# WizPoE-IO-V001.net
KiCad netlist of a schematic drawn in Altium Designer
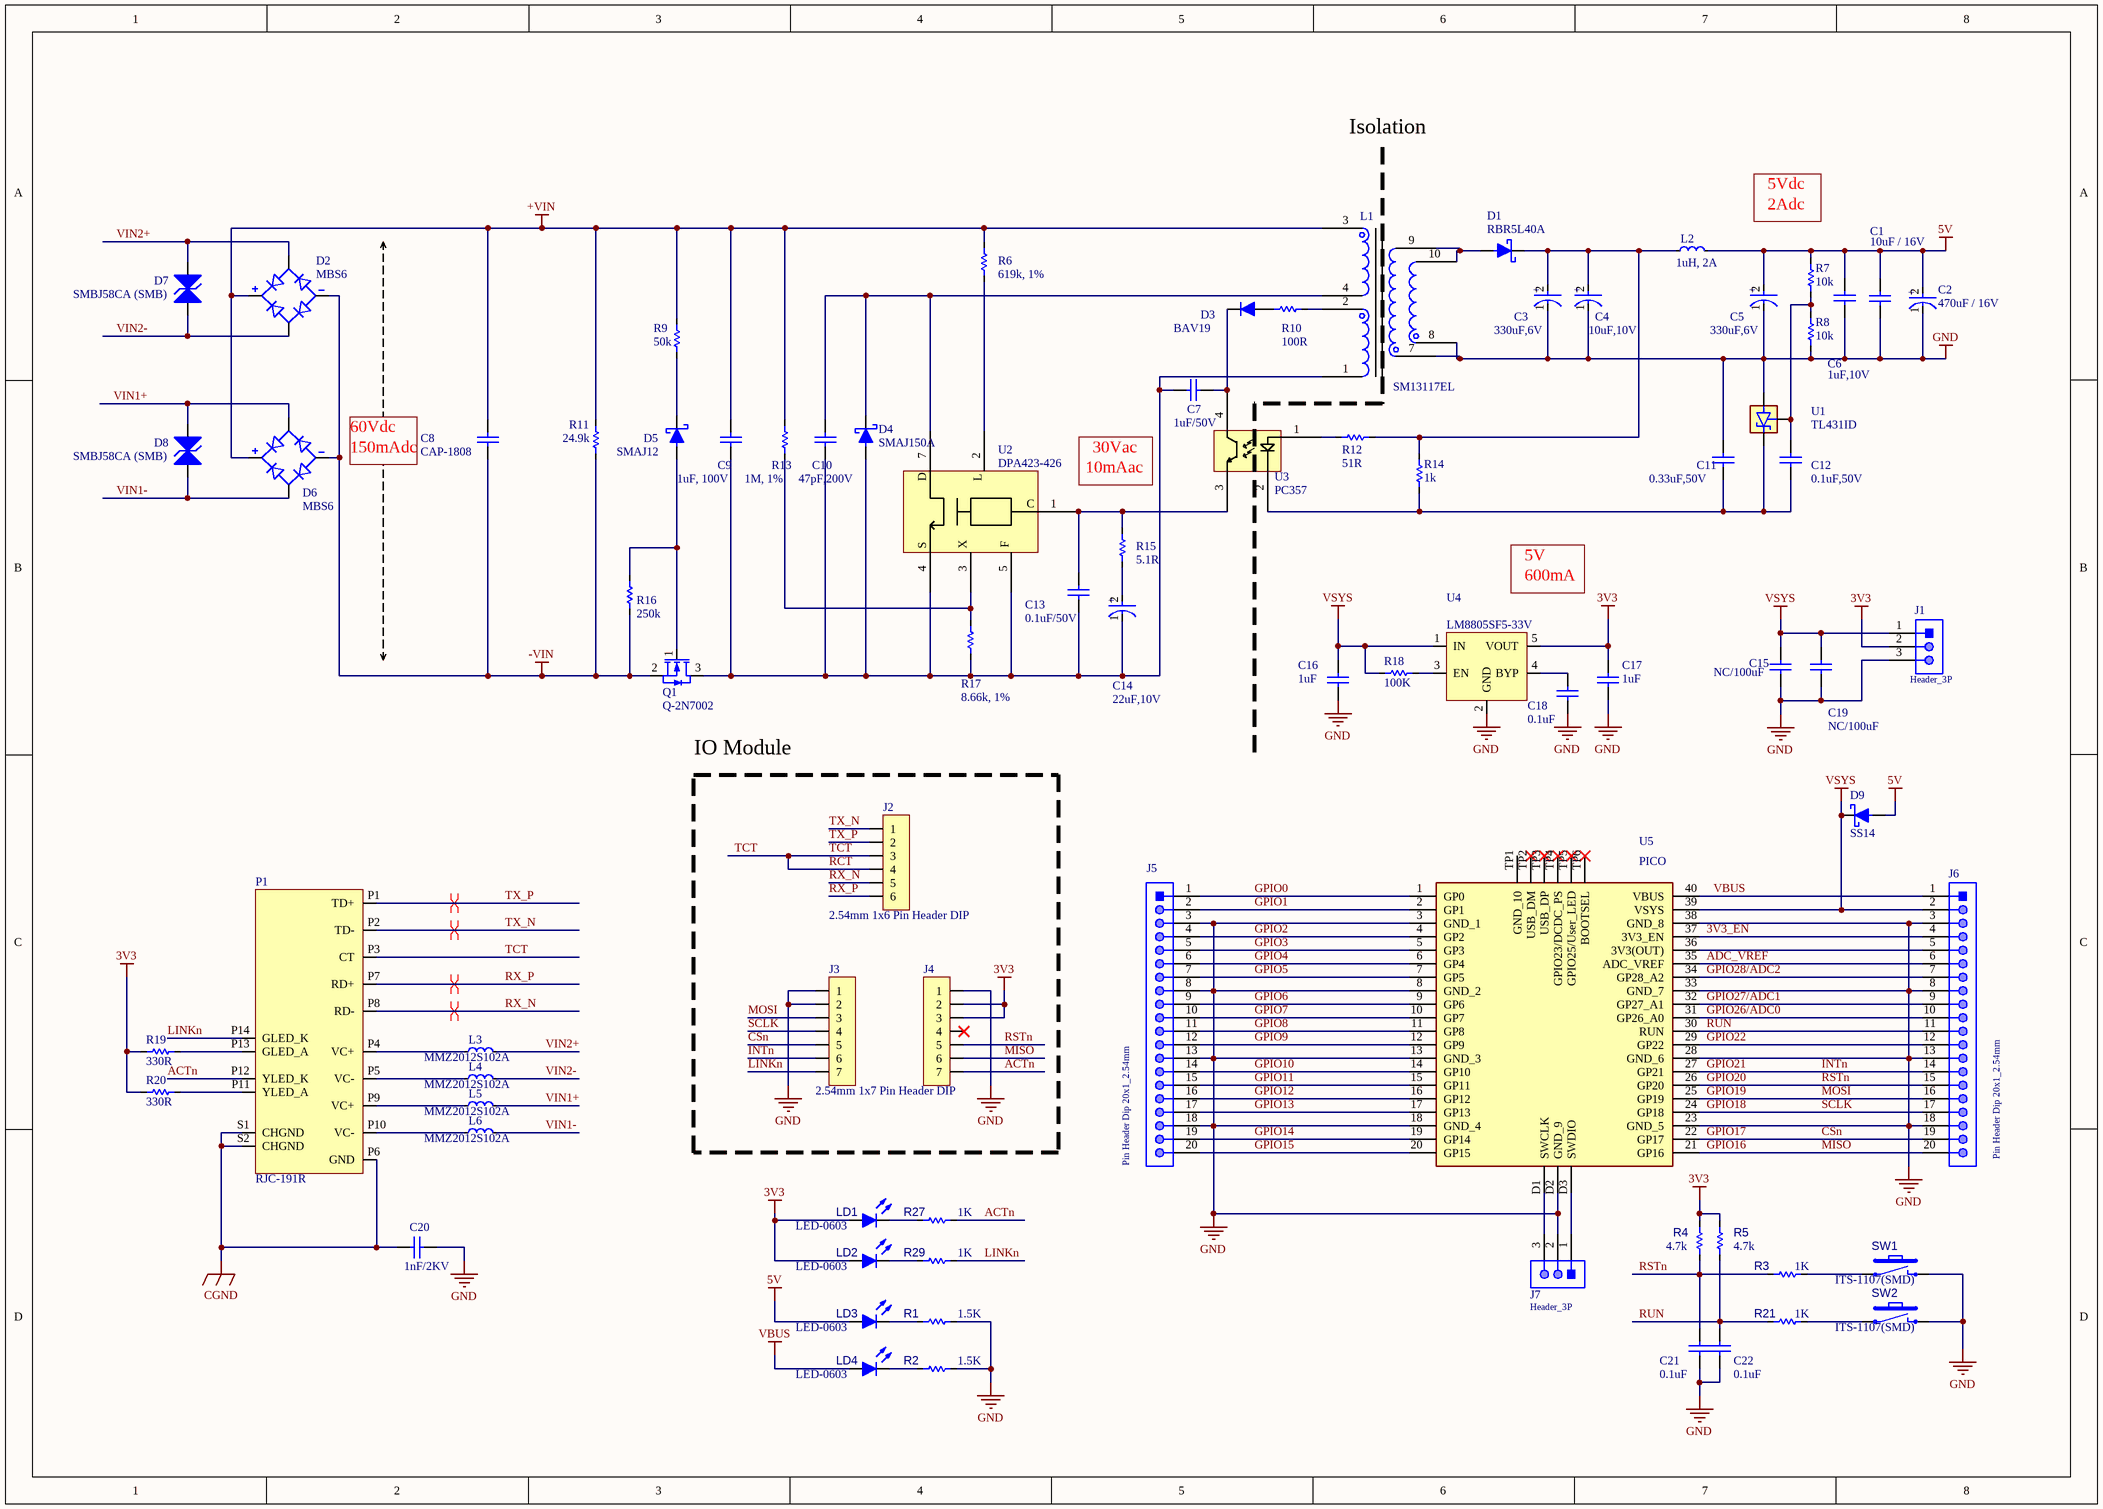
[diagram p0: WizPoE-IO-V001.SchDoc]

(export (version "E")
  (design (tool "Eeschema 10.0.6"))
  (components
    (comp (ref "C1")
      (value "10uF / 16V")
      (footprint "CAP-1808")
      (description "MLCC-1808(4520)")
      (libsource (lib "Alan_Lib") (part "CAP-1808"))
    )
    (comp (ref "C2")
      (value "470uF / 16V")
      (footprint "CAP-8.3EC")
      (description "AL-CAP D: 8.0mm SMD")
      (fields (field (name "VOLTAGE") "10V") (field (name "TOLERANCE") "20%"))
      (libsource (lib "Alan_Lib") (part "AL-CAP-D 8.0mm_SMD"))
    )
    (comp (ref "C3")
      (value "330uF,6V")
      (footprint "C6032TT(C)")
      (description "TANTAL_CASE A(3216)")
      (fields (field (name "VOLTAGE") "10V") (field (name "TOLERANCE") "20%"))
      (libsource (lib "Alan_Lib") (part "TANTAL_CASE A(3216)"))
    )
    (comp (ref "C4")
      (value "10uF,10V")
      (footprint "C3216TT(A)")
      (description "TANTAL_CASE A(3216)")
      (fields (field (name "VOLTAGE") "10V") (field (name "TOLERANCE") "20%"))
      (libsource (lib "Alan_Lib") (part "TANTAL_CASE A(3216)"))
    )
    (comp (ref "C5")
      (value "330uF,6V")
      (footprint "C3216TT(A)")
      (description "TANTAL_CASE A(3216)")
      (fields (field (name "VOLTAGE") "10V") (field (name "TOLERANCE") "20%"))
      (libsource (lib "Alan_Lib") (part "TANTAL_CASE A(3216)"))
    )
    (comp (ref "C6")
      (value "1uF,10V")
      (footprint "CAP-0603")
      (description "MLCC-0603(1608)")
      (libsource (lib "Alan_Lib") (part "CAP-0603"))
    )
    (comp (ref "C7")
      (value "1uF/50V")
      (footprint "CAP-0805")
      (description "MLCC-0805(2012)")
      (libsource (lib "Alan_Lib") (part "CAP-0805"))
    )
    (comp (ref "C8")
      (value "CAP-1808")
      (footprint "CAP-1808")
      (description "MLCC-1808(4520)")
      (libsource (lib "Alan_Lib") (part "CAP-1808"))
    )
    (comp (ref "C9")
      (value "1uF, 100V")
      (footprint "CAP-0805")
      (description "MLCC-0805(2012)")
      (libsource (lib "Alan_Lib") (part "CAP-0805"))
    )
    (comp (ref "C10")
      (value "47pF,200V")
      (footprint "CAP-0805")
      (description "MLCC-0805(2012)")
      (libsource (lib "Alan_Lib") (part "CAP-0805"))
    )
    (comp (ref "C11")
      (value "0.33uF,50V")
      (footprint "CAP-0603")
      (description "MLCC-0603(1608)")
      (libsource (lib "Alan_Lib") (part "CAP-0603"))
    )
    (comp (ref "C12")
      (value "0.1uF,50V")
      (footprint "CAP-0603")
      (description "MLCC-0603(1608)")
      (libsource (lib "Alan_Lib") (part "CAP-0603"))
    )
    (comp (ref "C13")
      (value "0.1uF/50V")
      (footprint "CAP-0805")
      (description "MLCC-0805(2012)")
      (libsource (lib "Alan_Lib") (part "CAP-0805"))
    )
    (comp (ref "C14")
      (value "22uF,10V")
      (footprint "C3216TT(A)")
      (description "TANTAL_CASE A(3216)")
      (fields (field (name "VOLTAGE") "10V") (field (name "TOLERANCE") "20%"))
      (libsource (lib "Alan_Lib") (part "TANTAL_CASE A(3216)"))
    )
    (comp (ref "C15")
      (value "NC/100uF")
      (footprint "CAP-1808")
      (description "MLCC-1808(4520)")
      (libsource (lib "Alan_Lib") (part "CAP-1808"))
    )
    (comp (ref "C16")
      (value "1uF")
      (footprint "CAP-0603")
      (description "MLCC-0603(1608)")
      (libsource (lib "Jaden_Lib") (part "CAP-0603"))
    )
    (comp (ref "C17")
      (value "1uF")
      (footprint "CAP-0603")
      (description "MLCC-0603(1608)")
      (libsource (lib "Jaden_Lib") (part "CAP-0603"))
    )
    (comp (ref "C18")
      (value "0.1uF")
      (footprint "CAP-0603")
      (description "MLCC-0603(1608)")
      (libsource (lib "Jaden_Lib") (part "CAP-0603"))
    )
    (comp (ref "C19")
      (value "NC/100uF")
      (footprint "CAP-1808")
      (description "MLCC-1808(4520)")
      (libsource (lib "Alan_Lib") (part "CAP-1808"))
    )
    (comp (ref "C20")
      (value "1nF/2KV")
      (footprint "CAP-1808")
      (description "MLCC-1808(4520)")
      (libsource (lib "Jaden_Lib") (part "CAP-1808"))
    )
    (comp (ref "C21")
      (value "0.1uF")
      (footprint "CAP-0603")
      (description "MLCC-0603(1608)")
      (libsource (lib "Jaden_Lib") (part "CAP-0603"))
    )
    (comp (ref "C22")
      (value "0.1uF")
      (footprint "CAP-0603")
      (description "MLCC-0603(1608)")
      (libsource (lib "Jaden_Lib") (part "CAP-0603"))
    )
    (comp (ref "D1")
      (value "RBR5L40A")
      (footprint "DO-214AB/SMC")
      (description "Silicon Schottky Diode")
      (libsource (lib "Alan_Lib") (part "DIODE-Shottky (SOD-323)"))
    )
    (comp (ref "D2") (value "MBS6") (footprint "TO-269AA(MBS)") (libsource (lib "Alan_Lib") (part "MBS6")))
    (comp (ref "D3")
      (value "BAV19")
      (footprint "SOD-123(1-C,2-A)")
      (description "Silicon Schottky Diode")
      (libsource (lib "Scott_lib") (part "DIODE-BAT60A"))
    )
    (comp (ref "D4")
      (value "SMAJ150A")
      (footprint "DO-214AC/SMA")
      (description "Silicon Schottky Diode")
      (libsource (lib "Alan_Lib") (part "DIODE-Shottky (SOD-323)"))
    )
    (comp (ref "D5")
      (value "SMAJ12")
      (footprint "DO-214AC/SMA")
      (description "Silicon Schottky Diode")
      (libsource (lib "Alan_Lib") (part "DIODE-Shottky (SOD-323)"))
    )
    (comp (ref "D6") (value "MBS6") (footprint "TO-269AA(MBS)") (libsource (lib "Alan_Lib") (part "MBS6")))
    (comp (ref "D7")
      (value "SMBJ58CA (SMB)")
      (footprint "DO-214AA/SMB(TVS)")
      (fields
        (field (name "PARTNUMBER") "SMAJ58CA-E3/61")
        (field (name "MANUFACTURER") "Vishay Semiconductor")
        (field (name "MANUFACTURER_1") "Vishay Semiconductors")
      )
      (libsource (lib "Jaden_Lib") (part "DIODE-TVS (SMB)"))
    )
    (comp (ref "D8")
      (value "SMBJ58CA (SMB)")
      (footprint "DO-214AA/SMB(TVS)")
      (fields
        (field (name "PARTNUMBER") "SMAJ58CA-E3/61")
        (field (name "MANUFACTURER") "Vishay Semiconductor")
        (field (name "MANUFACTURER_1") "Vishay Semiconductors")
      )
      (libsource (lib "Jaden_Lib") (part "DIODE-TVS (SMB)"))
    )
    (comp (ref "D9")
      (value "SS14")
      (footprint "DO-214AC/SMA")
      (description "DIODE SCHOTTKY 40V 1A SMA")
      (fields
        (field (name "MANUFACTURER") "ON Semiconductor")
        (field (name "OCTOPART") "https://octopart.com/ss14-on+semiconductor-29205033")
      )
      (libsource (lib "Jaden_Lib") (part "DIODE-Shottky SMA(DO-214AC)"))
    )
    (comp (ref "J1")
      (value "Header_3P")
      (footprint "IDC-1X3")
      (description "THT Vertical Pin Header WR-PHD, Pitch 2.54 mm, Single Row, 3 pins")
      (fields
        (field (name "PART NUMBER") "61300311121")
        (field (name "MANUFACTURER") "Wurth Elektronik")
        (field (name "PUBLISHER") "WurthElektronik")
      )
      (libsource (lib "Alan_Lib") (part "Pin Header 3x1_2.54mm"))
    )
    (comp (ref "J2")
      (value "2.54mm 1x6 Pin Header DIP")
      (footprint "IDC-1X6")
      (libsource (lib "Scott_lib") (part "2.54mm 1x6 Pin Header DIP"))
    )
    (comp (ref "J3")
      (value "2.54mm 1x7 Pin Header DIP")
      (footprint "IDC-1X7")
      (libsource (lib "") (part "2.54mm 1x7 Pin Header DIP_1"))
    )
    (comp (ref "J4")
      (value "2.54mm 1x7 Pin Header DIP")
      (footprint "IDC-1X7-1")
      (libsource (lib "Scott_lib") (part "2.54mm 1x7 Pin Header DIP"))
    )
    (comp (ref "J5")
      (value "Pin Header Dip 20x1_2.54mm")
      (footprint "IDC-1X20")
      (description "THT Vertical Pin Header WR-PHD, Pitch 2.54 mm, Single Row, 20 pins")
      (fields
        (field (name "MANUFACTURER") "Wurth Elektronik")
        (field (name "PART NUMBER") "61302011121")
        (field (name "PUBLISHER") "WurthElektronik")
      )
      (libsource (lib "Jaden_Lib") (part "Pin Header 20x1_2.54mm"))
    )
    (comp (ref "J6")
      (value "Pin Header Dip 20x1_2.54mm")
      (footprint "IDC-1X20")
      (description "THT Vertical Pin Header WR-PHD, Pitch 2.54 mm, Single Row, 20 pins")
      (fields
        (field (name "MANUFACTURER") "Wurth Elektronik")
        (field (name "PART NUMBER") "61302011121")
        (field (name "PUBLISHER") "WurthElektronik")
      )
      (libsource (lib "Jaden_Lib") (part "Pin Header 20x1_2.54mm"))
    )
    (comp (ref "J7")
      (value "Header_3P")
      (footprint "IDC-1X3")
      (description "THT Vertical Pin Header WR-PHD, Pitch 2.54 mm, Single Row, 3 pins")
      (fields
        (field (name "PART NUMBER") "61300311121")
        (field (name "MANUFACTURER") "Wurth Elektronik")
        (field (name "PUBLISHER") "WurthElektronik")
      )
      (libsource (lib "") (part "Pin Header 3x1_2.54mm_1"))
    )
    (comp (ref "L1")
      (value "SM13117EL")
      (footprint "SM13117EL")
      (libsource (lib "Alan_Lib") (part "SM13117EL"))
    )
    (comp (ref "L2")
      (value "1uH, 2A")
      (footprint "IND-0805")
      (description "Inductor 0805(2012)")
      (libsource (lib "Alan_Lib") (part "IND-0805"))
    )
    (comp (ref "L3")
      (value "MMZ2012S102A")
      (footprint "IND-0805")
      (description "Inductor 0603(1608)")
      (libsource (lib "Jaden_Lib") (part "IND-0603"))
    )
    (comp (ref "L4")
      (value "MMZ2012S102A")
      (footprint "IND-0805")
      (description "Inductor 0603(1608)")
      (libsource (lib "Jaden_Lib") (part "IND-0603"))
    )
    (comp (ref "L5")
      (value "MMZ2012S102A")
      (footprint "IND-0805")
      (description "Inductor 0603(1608)")
      (libsource (lib "Jaden_Lib") (part "IND-0603"))
    )
    (comp (ref "L6")
      (value "MMZ2012S102A")
      (footprint "IND-0805")
      (description "Inductor 0603(1608)")
      (libsource (lib "Jaden_Lib") (part "IND-0603"))
    )
    (comp (ref "LD1")
      (value "LED-0603")
      (footprint "LED-0603-RED")
      (libsource (lib "Scott_lib") (part "LED-0603"))
    )
    (comp (ref "LD2")
      (value "LED-0603")
      (footprint "LED-0603-RED")
      (libsource (lib "Scott_lib") (part "LED-0603"))
    )
    (comp (ref "LD3")
      (value "LED-0603")
      (footprint "LED-0603-RED")
      (libsource (lib "Scott_lib") (part "LED-0603"))
    )
    (comp (ref "LD4")
      (value "LED-0603")
      (footprint "LED-0603-RED")
      (libsource (lib "Scott_lib") (part "LED-0603"))
    )
    (comp (ref "P1")
      (value "RJC-191R")
      (footprint "RJC-191R")
      (description "PoE RJ45")
      (libsource (lib "Jaden_Lib") (part "RJC-191R"))
    )
    (comp (ref "Q1")
      (value "Q-2N7002")
      (footprint "SOT23-3L")
      (description "N-Channel 60-V (D-S) MOSFET")
      (libsource (lib "Alan_Lib") (part "Q-2N7002"))
    )
    (comp (ref "R1")
      (value "1.5K")
      (footprint "RES-0603")
      (description "RES0603")
      (libsource (lib "Scott_lib") (part "RES-0603"))
    )
    (comp (ref "R2")
      (value "1.5K")
      (footprint "RES-0603")
      (description "RES0603")
      (libsource (lib "Scott_lib") (part "RES-0603"))
    )
    (comp (ref "R3")
      (value "1K")
      (footprint "RES-0603")
      (description "RES0603")
      (libsource (lib "Alan_Lib") (part "RES-0603"))
    )
    (comp (ref "R4")
      (value "4.7k")
      (footprint "RES-0603")
      (description "RES0603")
      (libsource (lib "Alan_Lib") (part "RES-0603"))
    )
    (comp (ref "R5")
      (value "4.7k")
      (footprint "RES-0603")
      (description "RES0603")
      (libsource (lib "Alan_Lib") (part "RES-0603"))
    )
    (comp (ref "R6")
      (value "619k, 1%")
      (footprint "RES-0603")
      (description "Chip Resistor 0603(1608)")
      (fields (field (name "TOLERANCE") "1%") (field (name "MANUFACTURER") "Yageo"))
      (libsource (lib "Alan_Lib") (part "RES-0603"))
    )
    (comp (ref "R7")
      (value "10k")
      (footprint "RES-0603")
      (description "Chip Resistor 0603(1608)")
      (fields (field (name "TOLERANCE") "1%") (field (name "MANUFACTURER") "Yageo"))
      (libsource (lib "Alan_Lib") (part "RES-0603"))
    )
    (comp (ref "R8")
      (value "10k")
      (footprint "RES-0603")
      (description "Chip Resistor 0603(1608)")
      (fields (field (name "TOLERANCE") "1%") (field (name "MANUFACTURER") "Yageo"))
      (libsource (lib "Alan_Lib") (part "RES-0603"))
    )
    (comp (ref "R9")
      (value "50k")
      (footprint "RES-2012")
      (description "Chip Resistor 0805(2012)")
      (libsource (lib "Alan_Lib") (part "RES-2012"))
    )
    (comp (ref "R10")
      (value "100R")
      (footprint "RES-2012")
      (description "Chip Resistor 0805(2012)")
      (libsource (lib "Alan_Lib") (part "RES-2012"))
    )
    (comp (ref "R11")
      (value "24.9k")
      (footprint "RES-2012")
      (description "Chip Resistor 0805(2012)")
      (libsource (lib "Alan_Lib") (part "RES-2012"))
    )
    (comp (ref "R12")
      (value "51R")
      (footprint "RES-2012")
      (description "Chip Resistor 0805(2012)")
      (libsource (lib "Alan_Lib") (part "RES-2012"))
    )
    (comp (ref "R13")
      (value "1M, 1%")
      (footprint "RES-0603")
      (description "Chip Resistor 0603(1608)")
      (fields (field (name "TOLERANCE") "1%") (field (name "MANUFACTURER") "Yageo"))
      (libsource (lib "Alan_Lib") (part "RES-0603"))
    )
    (comp (ref "R14")
      (value "1k")
      (footprint "RES-2012")
      (description "Chip Resistor 0805(2012)")
      (libsource (lib "Alan_Lib") (part "RES-2012"))
    )
    (comp (ref "R15")
      (value "5.1R")
      (footprint "RES-2012")
      (description "Chip Resistor 0805(2012)")
      (libsource (lib "Alan_Lib") (part "RES-2012"))
    )
    (comp (ref "R16")
      (value "250k")
      (footprint "RES-2012")
      (description "Chip Resistor 0805(2012)")
      (libsource (lib "Alan_Lib") (part "RES-2012"))
    )
    (comp (ref "R17")
      (value "8.66k, 1%")
      (footprint "RES-0603")
      (description "Chip Resistor 0603(1608)")
      (fields (field (name "TOLERANCE") "1%") (field (name "MANUFACTURER") "Yageo"))
      (libsource (lib "Alan_Lib") (part "RES-0603"))
    )
    (comp (ref "R18")
      (value "100K")
      (footprint "RES-0603")
      (description "Chip Resistor 0603(1608)")
      (fields (field (name "TOLERANCE") "1%") (field (name "MANUFACTURER") "Yageo"))
      (libsource (lib "Jaden_Lib") (part "RES-0603"))
    )
    (comp (ref "R19")
      (value "330R")
      (footprint "RES-0603")
      (description "Chip Resistor 0603(1608)")
      (fields (field (name "TOLERANCE") "1%") (field (name "MANUFACTURER") "Yageo"))
      (libsource (lib "Jaden_Lib") (part "RES-0603"))
    )
    (comp (ref "R20")
      (value "330R")
      (footprint "RES-0603")
      (description "Chip Resistor 0603(1608)")
      (fields (field (name "TOLERANCE") "1%") (field (name "MANUFACTURER") "Yageo"))
      (libsource (lib "Jaden_Lib") (part "RES-0603"))
    )
    (comp (ref "R21")
      (value "1K")
      (footprint "RES-0603")
      (description "RES0603")
      (libsource (lib "Alan_Lib") (part "RES-0603"))
    )
    (comp (ref "R27")
      (value "1K")
      (footprint "RES-0603")
      (description "RES0603")
      (libsource (lib "Scott_lib") (part "RES-0603"))
    )
    (comp (ref "R29")
      (value "1K")
      (footprint "RES-0603")
      (description "RES0603")
      (libsource (lib "Scott_lib") (part "RES-0603"))
    )
    (comp (ref "SW1")
      (value "ITS-1107(SMD)")
      (footprint "IT-1107(SMD)")
      (description "TACT Switch (SMD)")
      (libsource (lib "Alan_Lib") (part "ITS-1107(SMD)"))
    )
    (comp (ref "SW2")
      (value "ITS-1107(SMD)")
      (footprint "IT-1107(SMD)")
      (description "TACT Switch (SMD)")
      (libsource (lib "Alan_Lib") (part "ITS-1107(SMD)"))
    )
    (comp (ref "U1")
      (value "TL431ID")
      (footprint "SOT23-3L")
      (description "Adjustable precision shunt regulator 3-SOT-23 -40 to 85")
      (fields (field (name "MF") "Texas Instruments") (field (name "MP") "TL431IDBZT"))
      (libsource (lib "Alan_Lib") (part "TL431IDBZT"))
    )
    (comp (ref "U2")
      (value "DPA423-426")
      (footprint "TO-263-7C")
      (description "Highly Integrated DC-DC Converter ICs for Power over Ethernet & Telecom Applications")
      (libsource (lib "Alan_Lib") (part "DPA423"))
    )
    (comp (ref "U3") (value "PC357") (footprint "PC357") (libsource (lib "Alan_Lib") (part "PC357")))
    (comp (ref "U4")
      (value "LM8805SF5-33V")
      (footprint "SOT-23-5L")
      (description "600mA CMOS LDO Regulator")
      (libsource (lib "Jaden_Lib") (part "LM8805SF5-33V"))
    )
    (comp (ref "U5")
      (value "PICO")
      (footprint "PICO")
      (description "Module")
      (libsource (lib "Jaden_Lib") (part "PICO"))
    )
  )
  (nets
    (net (code "1") (name "+VIN") (class "Default")
      (node (ref "C8") (pin "2") (pinfunction "2_2") (pintype "passive"))
      (node (ref "C9") (pin "2") (pinfunction "2_2") (pintype "passive"))
      (node (ref "D2") (pin "POS") (pinfunction "POS_POS") (pintype "passive"))
      (node (ref "D6") (pin "POS") (pinfunction "POS_POS") (pintype "passive"))
      (node (ref "L1") (pin "3") (pinfunction "3_3") (pintype "passive"))
      (node (ref "R11") (pin "2") (pinfunction "2_2") (pintype "passive"))
      (node (ref "R13") (pin "2") (pinfunction "2_2") (pintype "passive"))
      (node (ref "R6") (pin "2") (pinfunction "2_2") (pintype "passive"))
      (node (ref "R9") (pin "2") (pinfunction "2_2") (pintype "passive"))
    )
    (net (code "2") (name "-VIN") (class "Default")
      (node (ref "C8") (pin "1") (pinfunction "1_1") (pintype "passive"))
      (node (ref "D2") (pin "NEG") (pinfunction "NEG_NEG") (pintype "passive"))
      (node (ref "D6") (pin "NEG") (pinfunction "NEG_NEG") (pintype "passive"))
      (node (ref "Q1") (pin "2") (pinfunction "S_2") (pintype "passive"))
      (node (ref "R11") (pin "1") (pinfunction "1_1") (pintype "passive"))
      (node (ref "R16") (pin "1") (pinfunction "1_1") (pintype "passive"))
    )
    (net (code "3") (name "/3V3_EN") (class "Default")
      (node (ref "J6") (pin "4") (pinfunction "4_4") (pintype "passive"))
      (node (ref "U5") (pin "37") (pinfunction "3V3_EN_37") (pintype "passive"))
    )
    (net (code "4") (name "/ACTn") (class "Default")
      (node (ref "J4") (pin "7") (pinfunction "7_7") (pintype "passive"))
      (node (ref "P1") (pin "P12") (pinfunction "YLED_K_P12") (pintype "passive"))
      (node (ref "R27") (pin "1") (pinfunction "1_1") (pintype "passive"))
    )
    (net (code "5") (name "/ADC_VREF") (class "Default")
      (node (ref "J6") (pin "6") (pinfunction "6_6") (pintype "passive"))
      (node (ref "U5") (pin "35") (pinfunction "ADC_VREF_35") (pintype "passive"))
    )
    (net (code "6") (name "/CSn") (class "Default")
      (node (ref "J3") (pin "5") (pinfunction "5_5") (pintype "passive"))
      (node (ref "J6") (pin "19") (pinfunction "19_19") (pintype "passive"))
      (node (ref "U5") (pin "22") (pinfunction "GP17_22") (pintype "passive"))
    )
    (net (code "7") (name "/GPIO0") (class "Default")
      (node (ref "J5") (pin "1") (pinfunction "1_1") (pintype "passive"))
      (node (ref "U5") (pin "1") (pinfunction "GP0_1") (pintype "passive"))
    )
    (net (code "8") (name "/GPIO1") (class "Default")
      (node (ref "J5") (pin "2") (pinfunction "2_2") (pintype "passive"))
      (node (ref "U5") (pin "2") (pinfunction "GP1_2") (pintype "passive"))
    )
    (net (code "9") (name "/GPIO2") (class "Default")
      (node (ref "J5") (pin "4") (pinfunction "4_4") (pintype "passive"))
      (node (ref "U5") (pin "4") (pinfunction "GP2_4") (pintype "passive"))
    )
    (net (code "10") (name "/GPIO3") (class "Default")
      (node (ref "J5") (pin "5") (pinfunction "5_5") (pintype "passive"))
      (node (ref "U5") (pin "5") (pinfunction "GP3_5") (pintype "passive"))
    )
    (net (code "11") (name "/GPIO4") (class "Default")
      (node (ref "J5") (pin "6") (pinfunction "6_6") (pintype "passive"))
      (node (ref "U5") (pin "6") (pinfunction "GP4_6") (pintype "passive"))
    )
    (net (code "12") (name "/GPIO5") (class "Default")
      (node (ref "J5") (pin "7") (pinfunction "7_7") (pintype "passive"))
      (node (ref "U5") (pin "7") (pinfunction "GP5_7") (pintype "passive"))
    )
    (net (code "13") (name "/GPIO6") (class "Default")
      (node (ref "J5") (pin "9") (pinfunction "9_9") (pintype "passive"))
      (node (ref "U5") (pin "9") (pinfunction "GP6_9") (pintype "passive"))
    )
    (net (code "14") (name "/GPIO7") (class "Default")
      (node (ref "J5") (pin "10") (pinfunction "10_10") (pintype "passive"))
      (node (ref "U5") (pin "10") (pinfunction "GP7_10") (pintype "passive"))
    )
    (net (code "15") (name "/GPIO8") (class "Default")
      (node (ref "J5") (pin "11") (pinfunction "11_11") (pintype "passive"))
      (node (ref "U5") (pin "11") (pinfunction "GP8_11") (pintype "passive"))
    )
    (net (code "16") (name "/GPIO9") (class "Default")
      (node (ref "J5") (pin "12") (pinfunction "12_12") (pintype "passive"))
      (node (ref "U5") (pin "12") (pinfunction "GP9_12") (pintype "passive"))
    )
    (net (code "17") (name "/GPIO10") (class "Default")
      (node (ref "J5") (pin "14") (pinfunction "14_14") (pintype "passive"))
      (node (ref "U5") (pin "14") (pinfunction "GP10_14") (pintype "passive"))
    )
    (net (code "18") (name "/GPIO11") (class "Default")
      (node (ref "J5") (pin "15") (pinfunction "15_15") (pintype "passive"))
      (node (ref "U5") (pin "15") (pinfunction "GP11_15") (pintype "passive"))
    )
    (net (code "19") (name "/GPIO12") (class "Default")
      (node (ref "J5") (pin "16") (pinfunction "16_16") (pintype "passive"))
      (node (ref "U5") (pin "16") (pinfunction "GP12_16") (pintype "passive"))
    )
    (net (code "20") (name "/GPIO13") (class "Default")
      (node (ref "J5") (pin "17") (pinfunction "17_17") (pintype "passive"))
      (node (ref "U5") (pin "17") (pinfunction "GP13_17") (pintype "passive"))
    )
    (net (code "21") (name "/GPIO14") (class "Default")
      (node (ref "J5") (pin "19") (pinfunction "19_19") (pintype "passive"))
      (node (ref "U5") (pin "19") (pinfunction "GP14_19") (pintype "passive"))
    )
    (net (code "22") (name "/GPIO15") (class "Default")
      (node (ref "J5") (pin "20") (pinfunction "20_20") (pintype "passive"))
      (node (ref "U5") (pin "20") (pinfunction "GP15_20") (pintype "passive"))
    )
    (net (code "23") (name "/GPIO16") (class "Default")
      (node (ref "J4") (pin "6") (pinfunction "6_6") (pintype "passive"))
      (node (ref "J6") (pin "20") (pinfunction "20_20") (pintype "passive"))
      (node (ref "U5") (pin "21") (pinfunction "GP16_21") (pintype "passive"))
    )
    (net (code "24") (name "/GPIO18") (class "Default")
      (node (ref "J3") (pin "4") (pinfunction "4_4") (pintype "passive"))
      (node (ref "J6") (pin "17") (pinfunction "17_17") (pintype "passive"))
      (node (ref "U5") (pin "24") (pinfunction "GP18_24") (pintype "passive"))
    )
    (net (code "25") (name "/GPIO19") (class "Default")
      (node (ref "J3") (pin "3") (pinfunction "3_3") (pintype "passive"))
      (node (ref "J6") (pin "16") (pinfunction "16_16") (pintype "passive"))
      (node (ref "U5") (pin "25") (pinfunction "GP19_25") (pintype "passive"))
    )
    (net (code "26") (name "/GPIO20") (class "Default")
      (node (ref "C21") (pin "2") (pinfunction "2_2") (pintype "passive"))
      (node (ref "J4") (pin "5") (pinfunction "5_5") (pintype "passive"))
      (node (ref "J6") (pin "15") (pinfunction "15_15") (pintype "passive"))
      (node (ref "R3") (pin "2") (pinfunction "2_2") (pintype "passive"))
      (node (ref "R4") (pin "2") (pinfunction "2_2") (pintype "passive"))
      (node (ref "U5") (pin "26") (pinfunction "GP20_26") (pintype "passive"))
    )
    (net (code "27") (name "/GPIO21") (class "Default")
      (node (ref "J3") (pin "6") (pinfunction "6_6") (pintype "passive"))
      (node (ref "J6") (pin "14") (pinfunction "14_14") (pintype "passive"))
      (node (ref "U5") (pin "27") (pinfunction "GP21_27") (pintype "passive"))
    )
    (net (code "28") (name "/GPIO22") (class "Default")
      (node (ref "J6") (pin "12") (pinfunction "12_12") (pintype "passive"))
      (node (ref "U5") (pin "29") (pinfunction "GP22_29") (pintype "passive"))
    )
    (net (code "29") (name "/GPIO26{slash}ADC0") (class "Default")
      (node (ref "J6") (pin "10") (pinfunction "10_10") (pintype "passive"))
      (node (ref "U5") (pin "31") (pinfunction "GP26_A0_31") (pintype "passive"))
    )
    (net (code "30") (name "/GPIO27{slash}ADC1") (class "Default")
      (node (ref "J6") (pin "9") (pinfunction "9_9") (pintype "passive"))
      (node (ref "U5") (pin "32") (pinfunction "GP27_A1_32") (pintype "passive"))
    )
    (net (code "31") (name "/GPIO28{slash}ADC2") (class "Default")
      (node (ref "J6") (pin "7") (pinfunction "7_7") (pintype "passive"))
      (node (ref "U5") (pin "34") (pinfunction "GP28_A2_34") (pintype "passive"))
    )
    (net (code "32") (name "/LINKn") (class "Default")
      (node (ref "J3") (pin "7") (pinfunction "7_7") (pintype "passive"))
      (node (ref "P1") (pin "P14") (pinfunction "GLED_K_P14") (pintype "passive"))
      (node (ref "R29") (pin "1") (pinfunction "1_1") (pintype "passive"))
    )
    (net (code "33") (name "/RCT") (class "Default")
      (node (ref "J2") (pin "3") (pinfunction "3_3") (pintype "passive"))
      (node (ref "J2") (pin "4") (pinfunction "4_4") (pintype "passive"))
      (node (ref "P1") (pin "P3") (pinfunction "CT_P3") (pintype "passive"))
    )
    (net (code "34") (name "/RUN") (class "Default")
      (node (ref "C22") (pin "2") (pinfunction "2_2") (pintype "passive"))
      (node (ref "J6") (pin "11") (pinfunction "11_11") (pintype "passive"))
      (node (ref "R21") (pin "2") (pinfunction "2_2") (pintype "passive"))
      (node (ref "R5") (pin "2") (pinfunction "2_2") (pintype "passive"))
      (node (ref "U5") (pin "30") (pinfunction "RUN_30") (pintype "passive"))
    )
    (net (code "35") (name "/RX_N") (class "Default")
      (node (ref "J2") (pin "5") (pinfunction "5_5") (pintype "passive"))
      (node (ref "P1") (pin "P8") (pinfunction "RD-_P8") (pintype "passive"))
    )
    (net (code "36") (name "/RX_P") (class "Default")
      (node (ref "J2") (pin "6") (pinfunction "6_6") (pintype "passive"))
      (node (ref "P1") (pin "P7") (pinfunction "RD+_P7") (pintype "passive"))
    )
    (net (code "37") (name "/TX_N") (class "Default")
      (node (ref "J2") (pin "1") (pinfunction "1_1") (pintype "passive"))
      (node (ref "P1") (pin "P2") (pinfunction "TD-_P2") (pintype "passive"))
    )
    (net (code "38") (name "/TX_P") (class "Default")
      (node (ref "J2") (pin "2") (pinfunction "2_2") (pintype "passive"))
      (node (ref "P1") (pin "P1") (pinfunction "TD+_P1") (pintype "passive"))
    )
    (net (code "39") (name "/VIN1+") (class "Default")
      (node (ref "D6") (pin "AC1") (pinfunction "AC1_AC1") (pintype "passive"))
      (node (ref "D8") (pin "2") (pinfunction "A2_2") (pintype "passive"))
      (node (ref "L5") (pin "2") (pinfunction "2_2") (pintype "passive"))
    )
    (net (code "40") (name "/VIN1-") (class "Default")
      (node (ref "D6") (pin "AC2") (pinfunction "AC2_AC2") (pintype "passive"))
      (node (ref "D8") (pin "1") (pinfunction "A1_1") (pintype "passive"))
      (node (ref "L6") (pin "2") (pinfunction "2_2") (pintype "passive"))
    )
    (net (code "41") (name "/VIN2+") (class "Default")
      (node (ref "D2") (pin "AC1") (pinfunction "AC1_AC1") (pintype "passive"))
      (node (ref "D7") (pin "2") (pinfunction "A2_2") (pintype "passive"))
      (node (ref "L3") (pin "2") (pinfunction "2_2") (pintype "passive"))
    )
    (net (code "42") (name "/VIN2-") (class "Default")
      (node (ref "D2") (pin "AC2") (pinfunction "AC2_AC2") (pintype "passive"))
      (node (ref "D7") (pin "1") (pinfunction "A1_1") (pintype "passive"))
      (node (ref "L4") (pin "2") (pinfunction "2_2") (pintype "passive"))
    )
    (net (code "43") (name "3V3") (class "Default")
      (node (ref "C17") (pin "2") (pinfunction "2_2") (pintype "passive"))
      (node (ref "J1") (pin "2") (pinfunction "2_2") (pintype "passive"))
      (node (ref "J4") (pin "2") (pinfunction "2_2") (pintype "passive"))
      (node (ref "J4") (pin "3") (pinfunction "3_3") (pintype "passive"))
      (node (ref "LD1") (pin "1") (pinfunction "A_1") (pintype "passive"))
      (node (ref "LD2") (pin "1") (pinfunction "A_1") (pintype "passive"))
      (node (ref "R19") (pin "1") (pinfunction "1_1") (pintype "passive"))
      (node (ref "R20") (pin "2") (pinfunction "2_2") (pintype "passive"))
      (node (ref "R4") (pin "1") (pinfunction "1_1") (pintype "passive"))
      (node (ref "R5") (pin "1") (pinfunction "1_1") (pintype "passive"))
      (node (ref "U4") (pin "5") (pinfunction "VOUT_5") (pintype "power_in"))
    )
    (net (code "44") (name "5V") (class "Default")
      (node (ref "C1") (pin "1") (pinfunction "1_1") (pintype "passive"))
      (node (ref "C2") (pin "2") (pinfunction "A_2") (pintype "passive"))
      (node (ref "C5") (pin "2") (pinfunction "A_2") (pintype "passive"))
      (node (ref "C6") (pin "2") (pinfunction "2_2") (pintype "passive"))
      (node (ref "D9") (pin "1") (pinfunction "A_1") (pintype "passive"))
      (node (ref "L2") (pin "2") (pinfunction "2_2") (pintype "passive"))
      (node (ref "LD3") (pin "1") (pinfunction "A_1") (pintype "passive"))
      (node (ref "R7") (pin "1") (pinfunction "1_1") (pintype "passive"))
    )
    (net (code "45") (name "CGND") (class "Default")
      (node (ref "C20") (pin "1") (pinfunction "1_1") (pintype "passive"))
      (node (ref "P1") (pin "P6") (pinfunction "GND_P6") (pintype "passive"))
      (node (ref "P1") (pin "S1") (pinfunction "CHGND_S1") (pintype "passive"))
      (node (ref "P1") (pin "S2") (pinfunction "CHGND_S2") (pintype "passive"))
    )
    (net (code "46") (name "GND") (class "Default")
      (node (ref "C1") (pin "2") (pinfunction "2_2") (pintype "passive"))
      (node (ref "C11") (pin "2") (pinfunction "2_2") (pintype "passive"))
      (node (ref "C15") (pin "1") (pinfunction "1_1") (pintype "passive"))
      (node (ref "C16") (pin "1") (pinfunction "1_1") (pintype "passive"))
      (node (ref "C17") (pin "1") (pinfunction "1_1") (pintype "passive"))
      (node (ref "C18") (pin "1") (pinfunction "1_1") (pintype "passive"))
      (node (ref "C19") (pin "1") (pinfunction "1_1") (pintype "passive"))
      (node (ref "C2") (pin "1") (pinfunction "C_1") (pintype "passive"))
      (node (ref "C20") (pin "2") (pinfunction "2_2") (pintype "passive"))
      (node (ref "C21") (pin "1") (pinfunction "1_1") (pintype "passive"))
      (node (ref "C22") (pin "1") (pinfunction "1_1") (pintype "passive"))
      (node (ref "C3") (pin "1") (pinfunction "C_1") (pintype "passive"))
      (node (ref "C4") (pin "1") (pinfunction "C_1") (pintype "passive"))
      (node (ref "C5") (pin "1") (pinfunction "C_1") (pintype "passive"))
      (node (ref "C6") (pin "1") (pinfunction "1_1") (pintype "passive"))
      (node (ref "J1") (pin "3") (pinfunction "3_3") (pintype "passive"))
      (node (ref "J3") (pin "1") (pinfunction "1_1") (pintype "passive"))
      (node (ref "J3") (pin "2") (pinfunction "2_2") (pintype "passive"))
      (node (ref "J4") (pin "1") (pinfunction "1_1") (pintype "passive"))
      (node (ref "J5") (pin "13") (pinfunction "13_13") (pintype "passive"))
      (node (ref "J5") (pin "18") (pinfunction "18_18") (pintype "passive"))
      (node (ref "J5") (pin "3") (pinfunction "3_3") (pintype "passive"))
      (node (ref "J5") (pin "8") (pinfunction "8_8") (pintype "passive"))
      (node (ref "J6") (pin "13") (pinfunction "13_13") (pintype "passive"))
      (node (ref "J6") (pin "18") (pinfunction "18_18") (pintype "passive"))
      (node (ref "J6") (pin "3") (pinfunction "3_3") (pintype "passive"))
      (node (ref "J6") (pin "8") (pinfunction "8_8") (pintype "passive"))
      (node (ref "J7") (pin "2") (pinfunction "2_2") (pintype "passive"))
      (node (ref "L1") (pin "7") (pinfunction "7_7") (pintype "passive"))
      (node (ref "L1") (pin "8") (pinfunction "8_8") (pintype "passive"))
      (node (ref "R1") (pin "1") (pinfunction "1_1") (pintype "passive"))
      (node (ref "R2") (pin "1") (pinfunction "1_1") (pintype "passive"))
      (node (ref "R8") (pin "2") (pinfunction "2_2") (pintype "passive"))
      (node (ref "SW1") (pin "2") (pintype "passive"))
      (node (ref "SW2") (pin "2") (pintype "passive"))
      (node (ref "U1") (pin "3") (pinfunction "ANODE_3") (pintype "passive"))
      (node (ref "U4") (pin "2") (pinfunction "GND_2") (pintype "power_in"))
      (node (ref "U5") (pin "13") (pinfunction "GND_3_13") (pintype "passive"))
      (node (ref "U5") (pin "18") (pinfunction "GND_4_18") (pintype "passive"))
      (node (ref "U5") (pin "23") (pinfunction "GND_5_23") (pintype "passive"))
      (node (ref "U5") (pin "28") (pinfunction "GND_6_28") (pintype "passive"))
      (node (ref "U5") (pin "3") (pinfunction "GND_1_3") (pintype "passive"))
      (node (ref "U5") (pin "33") (pinfunction "GND_7_33") (pintype "passive"))
      (node (ref "U5") (pin "38") (pinfunction "GND_8_38") (pintype "passive"))
      (node (ref "U5") (pin "8") (pinfunction "GND_2_8") (pintype "passive"))
      (node (ref "U5") (pin "D2") (pinfunction "GND_9_D2") (pintype "passive"))
    )
    (net (code "47") (name "Net-(C3-A)") (class "Default")
      (node (ref "C3") (pin "2") (pinfunction "A_2") (pintype "passive"))
      (node (ref "C4") (pin "2") (pinfunction "A_2") (pintype "passive"))
      (node (ref "D1") (pin "2") (pinfunction "K_2") (pintype "passive"))
      (node (ref "L2") (pin "1") (pinfunction "1_1") (pintype "passive"))
      (node (ref "R12") (pin "1") (pinfunction "1_1") (pintype "passive"))
      (node (ref "R14") (pin "1") (pinfunction "1_1") (pintype "passive"))
    )
    (net (code "48") (name "Net-(C14-A)") (class "Default")
      (node (ref "C14") (pin "2") (pinfunction "A_2") (pintype "passive"))
      (node (ref "R15") (pin "1") (pinfunction "1_1") (pintype "passive"))
    )
    (net (code "49") (name "Net-(C14-C)") (class "Default")
      (node (ref "C10") (pin "1") (pinfunction "1_1") (pintype "passive"))
      (node (ref "C13") (pin "1") (pinfunction "1_1") (pintype "passive"))
      (node (ref "C14") (pin "1") (pinfunction "C_1") (pintype "passive"))
      (node (ref "C7") (pin "2") (pinfunction "2_2") (pintype "passive"))
      (node (ref "C9") (pin "1") (pinfunction "1_1") (pintype "passive"))
      (node (ref "D4") (pin "1") (pinfunction "A_1") (pintype "passive"))
      (node (ref "L1") (pin "1") (pinfunction "1_1") (pintype "passive"))
      (node (ref "Q1") (pin "3") (pinfunction "D_3") (pintype "passive"))
      (node (ref "R17") (pin "1") (pinfunction "1_1") (pintype "passive"))
      (node (ref "U2") (pin "4") (pinfunction "S_4") (pintype "passive"))
      (node (ref "U2") (pin "5") (pinfunction "F_5") (pintype "passive"))
    )
    (net (code "50") (name "Net-(D1-A)") (class "Default")
      (node (ref "D1") (pin "1") (pinfunction "A_1") (pintype "passive"))
      (node (ref "L1") (pin "10") (pinfunction "10_10") (pintype "passive"))
      (node (ref "L1") (pin "9") (pinfunction "9_9") (pintype "passive"))
    )
    (net (code "51") (name "Net-(D3-A)") (class "Default")
      (node (ref "D3") (pin "2") (pinfunction "A_2") (pintype "passive"))
      (node (ref "R10") (pin "2") (pinfunction "2_2") (pintype "passive"))
    )
    (net (code "52") (name "Net-(D3-K)") (class "Default")
      (node (ref "C7") (pin "1") (pinfunction "1_1") (pintype "passive"))
      (node (ref "D3") (pin "1") (pinfunction "K_1") (pintype "passive"))
      (node (ref "U3") (pin "4") (pintype "passive"))
    )
    (net (code "53") (name "Net-(D4-K)") (class "Default")
      (node (ref "C10") (pin "2") (pinfunction "2_2") (pintype "passive"))
      (node (ref "D4") (pin "2") (pinfunction "K_2") (pintype "passive"))
      (node (ref "L1") (pin "4") (pinfunction "4_4") (pintype "passive"))
      (node (ref "U2") (pin "7") (pinfunction "D_7") (pintype "passive"))
    )
    (net (code "54") (name "Net-(D5-A)") (class "Default")
      (node (ref "D5") (pin "1") (pinfunction "A_1") (pintype "passive"))
      (node (ref "Q1") (pin "1") (pinfunction "G_1") (pintype "passive"))
      (node (ref "R16") (pin "2") (pinfunction "2_2") (pintype "passive"))
    )
    (net (code "55") (name "Net-(D5-K)") (class "Default")
      (node (ref "D5") (pin "2") (pinfunction "K_2") (pintype "passive"))
      (node (ref "R9") (pin "1") (pinfunction "1_1") (pintype "passive"))
    )
    (net (code "56") (name "Net-(L1-Pad2)") (class "Default")
      (node (ref "L1") (pin "2") (pinfunction "2_2") (pintype "passive"))
      (node (ref "R10") (pin "1") (pinfunction "1_1") (pintype "passive"))
    )
    (net (code "57") (name "Net-(L3-Pad1)") (class "Default")
      (node (ref "L3") (pin "1") (pinfunction "1_1") (pintype "passive"))
      (node (ref "P1") (pin "P4") (pinfunction "VC+_P4") (pintype "passive"))
    )
    (net (code "58") (name "Net-(L4-Pad1)") (class "Default")
      (node (ref "L4") (pin "1") (pinfunction "1_1") (pintype "passive"))
      (node (ref "P1") (pin "P5") (pinfunction "VC-_P5") (pintype "passive"))
    )
    (net (code "59") (name "Net-(L5-Pad1)") (class "Default")
      (node (ref "L5") (pin "1") (pinfunction "1_1") (pintype "passive"))
      (node (ref "P1") (pin "P9") (pinfunction "VC+_P9") (pintype "passive"))
    )
    (net (code "60") (name "Net-(L6-Pad1)") (class "Default")
      (node (ref "L6") (pin "1") (pinfunction "1_1") (pintype "passive"))
      (node (ref "P1") (pin "P10") (pinfunction "VC-_P10") (pintype "passive"))
    )
    (net (code "61") (name "Net-(LD1-K)") (class "Default")
      (node (ref "LD1") (pin "2") (pinfunction "K_2") (pintype "passive"))
      (node (ref "R27") (pin "2") (pinfunction "2_2") (pintype "passive"))
    )
    (net (code "62") (name "Net-(LD2-K)") (class "Default")
      (node (ref "LD2") (pin "2") (pinfunction "K_2") (pintype "passive"))
      (node (ref "R29") (pin "2") (pinfunction "2_2") (pintype "passive"))
    )
    (net (code "63") (name "Net-(LD3-K)") (class "Default")
      (node (ref "LD3") (pin "2") (pinfunction "K_2") (pintype "passive"))
      (node (ref "R1") (pin "2") (pinfunction "2_2") (pintype "passive"))
    )
    (net (code "64") (name "Net-(LD4-K)") (class "Default")
      (node (ref "LD4") (pin "2") (pinfunction "K_2") (pintype "passive"))
      (node (ref "R2") (pin "2") (pinfunction "2_2") (pintype "passive"))
    )
    (net (code "65") (name "Net-(P1-GLED_A)") (class "Default")
      (node (ref "P1") (pin "P13") (pinfunction "GLED_A_P13") (pintype "passive"))
      (node (ref "R19") (pin "2") (pinfunction "2_2") (pintype "passive"))
    )
    (net (code "66") (name "Net-(P1-YLED_A)") (class "Default")
      (node (ref "P1") (pin "P11") (pinfunction "YLED_A_P11") (pintype "passive"))
      (node (ref "R20") (pin "1") (pinfunction "1_1") (pintype "passive"))
    )
    (net (code "67") (name "Net-(R3-Pad1)") (class "Default")
      (node (ref "R3") (pin "1") (pinfunction "1_1") (pintype "passive"))
      (node (ref "SW1") (pin "1") (pintype "passive"))
    )
    (net (code "68") (name "Net-(R12-Pad2)") (class "Default")
      (node (ref "R12") (pin "2") (pinfunction "2_2") (pintype "passive"))
      (node (ref "U3") (pin "1") (pintype "passive"))
    )
    (net (code "69") (name "Net-(R21-Pad1)") (class "Default")
      (node (ref "R21") (pin "1") (pinfunction "1_1") (pintype "passive"))
      (node (ref "SW2") (pin "1") (pintype "passive"))
    )
    (net (code "70") (name "Net-(U1-CATHODE)") (class "Default")
      (node (ref "C11") (pin "1") (pinfunction "1_1") (pintype "passive"))
      (node (ref "C12") (pin "1") (pinfunction "1_1") (pintype "passive"))
      (node (ref "R14") (pin "2") (pinfunction "2_2") (pintype "passive"))
      (node (ref "U1") (pin "1") (pinfunction "CATHODE_1") (pintype "passive"))
      (node (ref "U3") (pin "2") (pintype "passive"))
    )
    (net (code "71") (name "Net-(U1-REF)") (class "Default")
      (node (ref "C12") (pin "2") (pinfunction "2_2") (pintype "passive"))
      (node (ref "R7") (pin "2") (pinfunction "2_2") (pintype "passive"))
      (node (ref "R8") (pin "1") (pinfunction "1_1") (pintype "passive"))
      (node (ref "U1") (pin "2") (pinfunction "REF_2") (pintype "passive"))
    )
    (net (code "72") (name "Net-(U2-C)") (class "Default")
      (node (ref "C13") (pin "2") (pinfunction "2_2") (pintype "passive"))
      (node (ref "R15") (pin "2") (pinfunction "2_2") (pintype "passive"))
      (node (ref "U2") (pin "1") (pinfunction "C_1") (pintype "passive"))
      (node (ref "U3") (pin "3") (pintype "passive"))
    )
    (net (code "73") (name "Net-(U2-L)") (class "Default")
      (node (ref "R6") (pin "1") (pinfunction "1_1") (pintype "passive"))
      (node (ref "U2") (pin "2") (pinfunction "L_2") (pintype "passive"))
    )
    (net (code "74") (name "Net-(U2-X)") (class "Default")
      (node (ref "R13") (pin "1") (pinfunction "1_1") (pintype "passive"))
      (node (ref "R17") (pin "2") (pinfunction "2_2") (pintype "passive"))
      (node (ref "U2") (pin "3") (pinfunction "X_3") (pintype "passive"))
    )
    (net (code "75") (name "Net-(U4-BYP)") (class "Default")
      (node (ref "C18") (pin "2") (pinfunction "2_2") (pintype "passive"))
      (node (ref "U4") (pin "4") (pinfunction "BYP_4") (pintype "power_in"))
    )
    (net (code "76") (name "Net-(U4-EN)") (class "Default")
      (node (ref "R18") (pin "2") (pinfunction "2_2") (pintype "passive"))
      (node (ref "U4") (pin "3") (pinfunction "EN_3") (pintype "power_in"))
    )
    (net (code "77") (name "Net-(U5-3V3(OUT))") (class "Default")
      (node (ref "J6") (pin "5") (pinfunction "5_5") (pintype "passive"))
      (node (ref "U5") (pin "36") (pinfunction "3V3(OUT)_36") (pintype "passive"))
    )
    (net (code "78") (name "Net-(U5-SWCLK)") (class "Default")
      (node (ref "J7") (pin "3") (pinfunction "3_3") (pintype "passive"))
      (node (ref "U5") (pin "D1") (pinfunction "SWCLK_D1") (pintype "passive"))
    )
    (net (code "79") (name "Net-(U5-SWDIO)") (class "Default")
      (node (ref "J7") (pin "1") (pinfunction "1_1") (pintype "passive"))
      (node (ref "U5") (pin "D3") (pinfunction "SWDIO_D3") (pintype "passive"))
    )
    (net (code "80") (name "VBUS") (class "Default")
      (node (ref "J6") (pin "1") (pinfunction "1_1") (pintype "passive"))
      (node (ref "LD4") (pin "1") (pinfunction "A_1") (pintype "passive"))
      (node (ref "U5") (pin "40") (pinfunction "VBUS_40") (pintype "passive"))
    )
    (net (code "81") (name "VSYS") (class "Default")
      (node (ref "C15") (pin "2") (pinfunction "2_2") (pintype "passive"))
      (node (ref "C16") (pin "2") (pinfunction "2_2") (pintype "passive"))
      (node (ref "C19") (pin "2") (pinfunction "2_2") (pintype "passive"))
      (node (ref "D9") (pin "2") (pinfunction "C_2") (pintype "passive"))
      (node (ref "J1") (pin "1") (pinfunction "1_1") (pintype "passive"))
      (node (ref "J6") (pin "2") (pinfunction "2_2") (pintype "passive"))
      (node (ref "R18") (pin "1") (pinfunction "1_1") (pintype "passive"))
      (node (ref "U4") (pin "1") (pinfunction "IN_1") (pintype "power_in"))
      (node (ref "U5") (pin "39") (pinfunction "VSYS_39") (pintype "passive"))
    )
    (net (code "82") (name "unconnected-(J4-Pad4)") (class "Default")
      (node (ref "J4") (pin "4") (pinfunction "4_4") (pintype "passive+no_connect"))
    )
    (net (code "83") (name "unconnected-(U5-BOOTSEL-PadTP6)") (class "Default")
      (node (ref "U5") (pin "TP6") (pinfunction "BOOTSEL_TP6") (pintype "passive+no_connect"))
    )
    (net (code "84") (name "unconnected-(U5-GND_10-PadTP1)") (class "Default")
      (node (ref "U5") (pin "TP1") (pinfunction "GND_10_TP1") (pintype "passive"))
    )
    (net (code "85") (name "unconnected-(U5-GPIO23{slash}DCDC_PS-PadTP4)") (class "Default")
      (node (ref "U5") (pin "TP4") (pinfunction "GPIO23/DCDC_PS_TP4") (pintype "passive+no_connect"))
    )
    (net (code "86") (name "unconnected-(U5-GPIO25{slash}User_LED-PadTP5)") (class "Default")
      (node (ref "U5") (pin "TP5") (pinfunction "GPIO25/User_LED_TP5") (pintype "passive+no_connect"))
    )
    (net (code "87") (name "unconnected-(U5-USB_DM-PadTP2)") (class "Default")
      (node (ref "U5") (pin "TP2") (pinfunction "USB_DM_TP2") (pintype "passive+no_connect"))
    )
    (net (code "88") (name "unconnected-(U5-USB_DP-PadTP3)") (class "Default")
      (node (ref "U5") (pin "TP3") (pinfunction "USB_DP_TP3") (pintype "passive+no_connect"))
    )
  )
)
